# it6251_core.net
KiCad netlist of a schematic drawn in Altium Designer
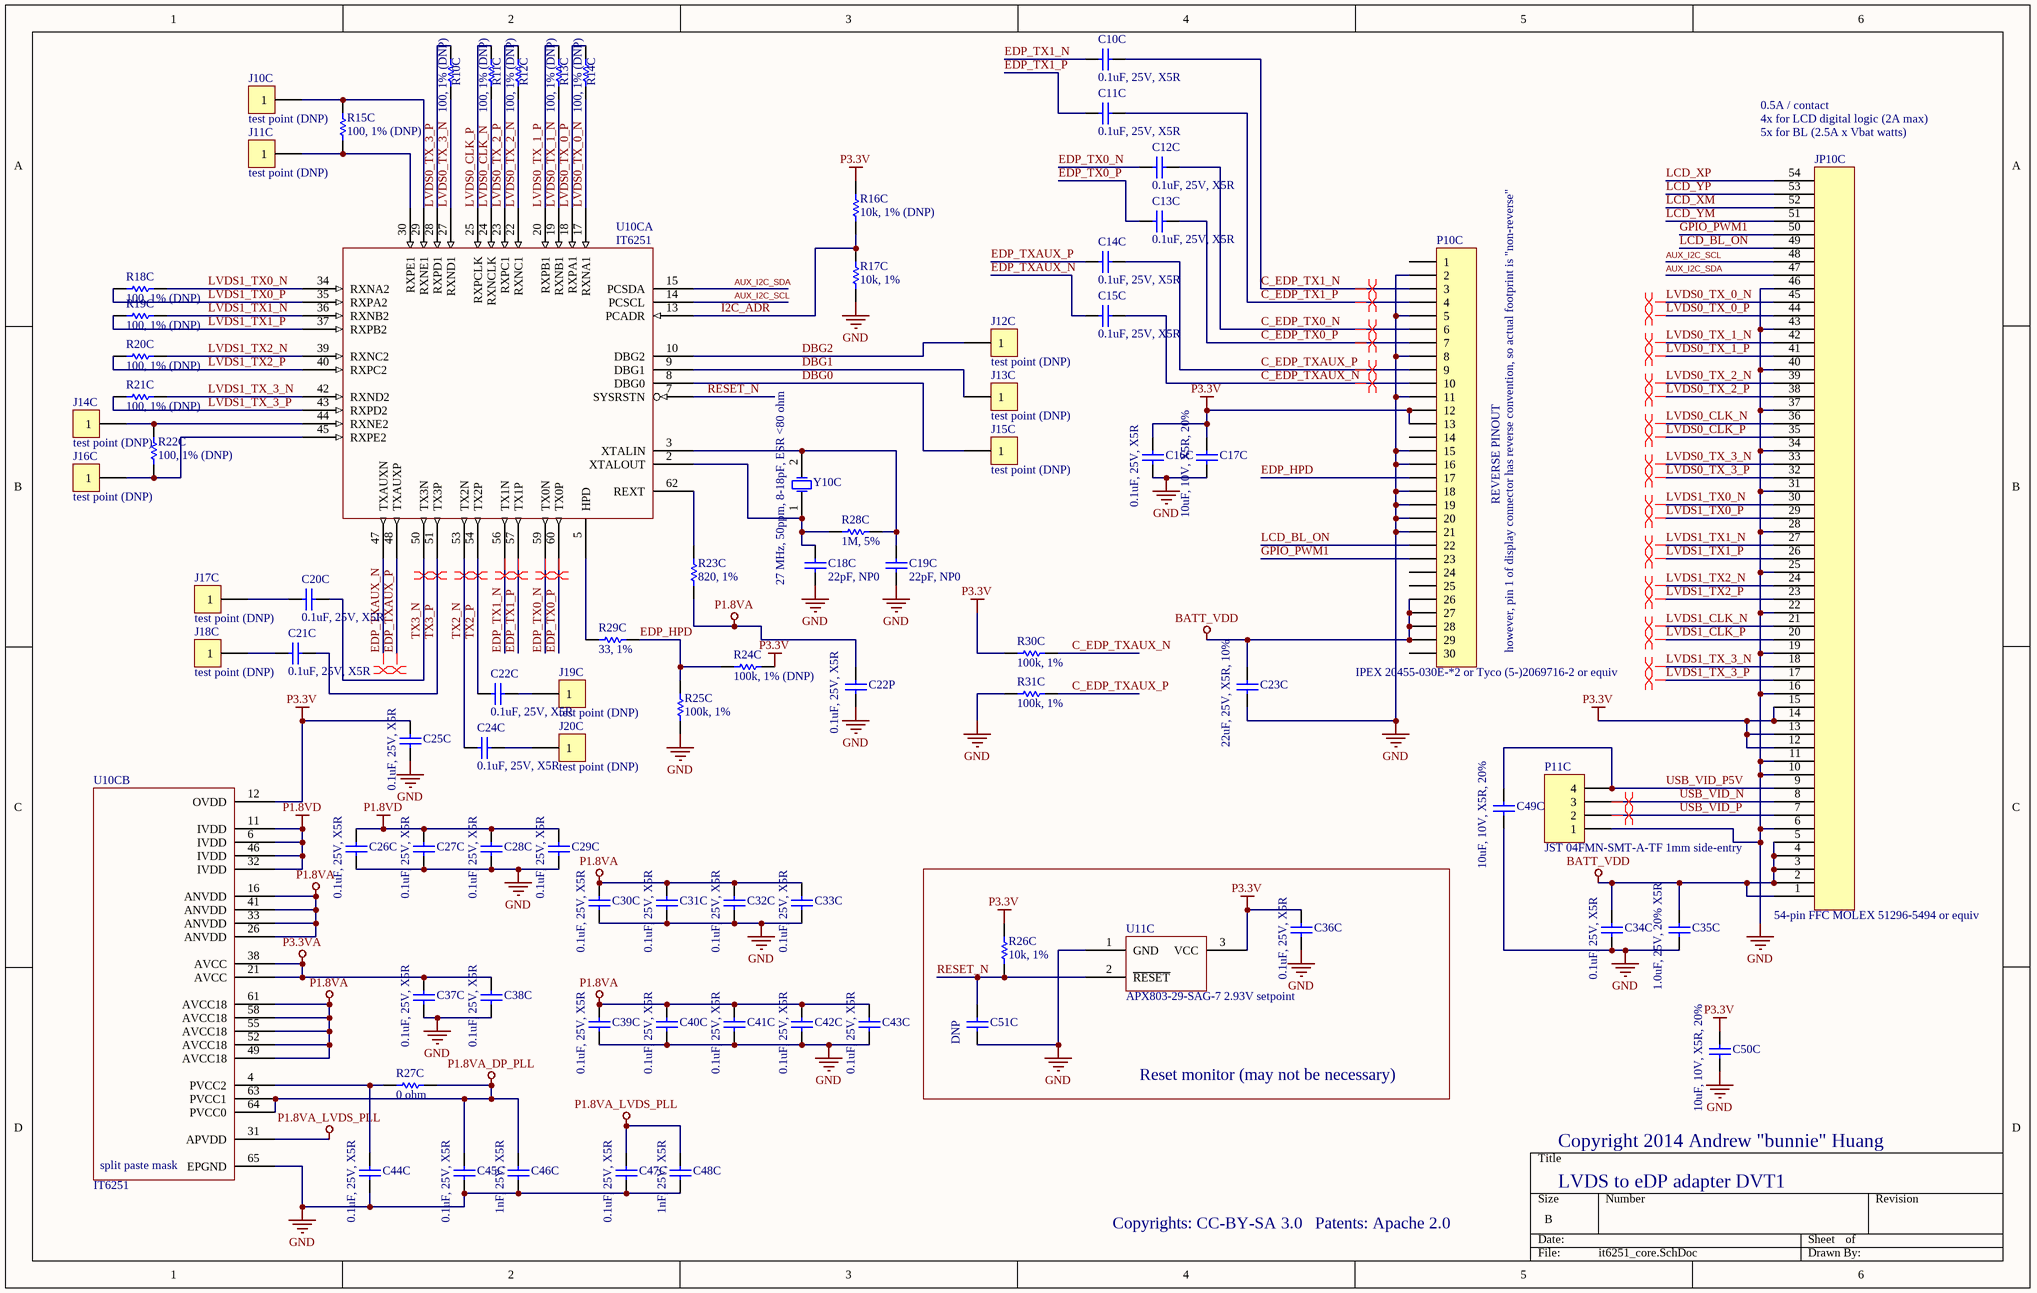
[diagram p0: it6251_core.SchDoc]

(export (version "E")
  (design (tool "Eeschema 10.0.6"))
  (components
    (comp (ref "C10C")
      (value "0.1uF, 25V, X5R")
      (footprint "CAPC1005N")
      (description "Capacitor (Semiconductor SIM Model)")
      (fields (field (name "PUBLISHER") "Altium Limited"))
      (libsource (lib "Miscellaneous Devices") (part "Cap Semi"))
    )
    (comp (ref "C11C")
      (value "0.1uF, 25V, X5R")
      (footprint "CAPC1005N")
      (description "Capacitor (Semiconductor SIM Model)")
      (fields (field (name "PUBLISHER") "Altium Limited"))
      (libsource (lib "Miscellaneous Devices") (part "Cap Semi"))
    )
    (comp (ref "C12C")
      (value "0.1uF, 25V, X5R")
      (footprint "CAPC1005N")
      (description "Capacitor (Semiconductor SIM Model)")
      (fields (field (name "PUBLISHER") "Altium Limited"))
      (libsource (lib "Miscellaneous Devices") (part "Cap Semi"))
    )
    (comp (ref "C13C")
      (value "0.1uF, 25V, X5R")
      (footprint "CAPC1005N")
      (description "Capacitor (Semiconductor SIM Model)")
      (fields (field (name "PUBLISHER") "Altium Limited"))
      (libsource (lib "Miscellaneous Devices") (part "Cap Semi"))
    )
    (comp (ref "C14C")
      (value "0.1uF, 25V, X5R")
      (footprint "CAPC1005N")
      (description "Capacitor (Semiconductor SIM Model)")
      (fields (field (name "PUBLISHER") "Altium Limited"))
      (libsource (lib "Miscellaneous Devices") (part "Cap Semi"))
    )
    (comp (ref "C15C")
      (value "0.1uF, 25V, X5R")
      (footprint "CAPC1005N")
      (description "Capacitor (Semiconductor SIM Model)")
      (fields (field (name "PUBLISHER") "Altium Limited"))
      (libsource (lib "Miscellaneous Devices") (part "Cap Semi"))
    )
    (comp (ref "C16C")
      (value "0.1uF, 25V, X5R")
      (footprint "CAPC1005N")
      (description "Capacitor (Semiconductor SIM Model)")
      (fields (field (name "PUBLISHER") "Altium Limited"))
      (libsource (lib "Miscellaneous Devices") (part "Cap Semi"))
    )
    (comp (ref "C17C")
      (value "10uF, 10V, X5R, 20%")
      (footprint "CAPC1608N")
      (description "Capacitor (Semiconductor SIM Model)")
      (fields (field (name "PUBLISHER") "Altium Limited"))
      (libsource (lib "Miscellaneous Devices") (part "Cap Semi"))
    )
    (comp (ref "C18C")
      (value "22pF, NP0")
      (footprint "CAPC1005N")
      (description "Capacitor (Semiconductor SIM Model)")
      (fields (field (name "PUBLISHER") "Altium Limited"))
      (libsource (lib "Miscellaneous Devices") (part "Cap Semi"))
    )
    (comp (ref "C19C")
      (value "22pF, NP0")
      (footprint "CAPC1005N")
      (description "Capacitor (Semiconductor SIM Model)")
      (fields (field (name "PUBLISHER") "Altium Limited"))
      (libsource (lib "Miscellaneous Devices") (part "Cap Semi"))
    )
    (comp (ref "C20C")
      (value "0.1uF, 25V, X5R")
      (footprint "CAPC1005N")
      (description "Capacitor (Semiconductor SIM Model)")
      (fields (field (name "PUBLISHER") "Altium Limited"))
      (libsource (lib "Miscellaneous Devices") (part "Cap Semi"))
    )
    (comp (ref "C21C")
      (value "0.1uF, 25V, X5R")
      (footprint "CAPC1005N")
      (description "Capacitor (Semiconductor SIM Model)")
      (fields (field (name "PUBLISHER") "Altium Limited"))
      (libsource (lib "Miscellaneous Devices") (part "Cap Semi"))
    )
    (comp (ref "C22C")
      (value "0.1uF, 25V, X5R")
      (footprint "CAPC1005N")
      (description "Capacitor (Semiconductor SIM Model)")
      (fields (field (name "PUBLISHER") "Altium Limited"))
      (libsource (lib "Miscellaneous Devices") (part "Cap Semi"))
    )
    (comp (ref "C22P")
      (value "0.1uF, 25V, X5R")
      (footprint "CAPC1005N")
      (description "Capacitor (Semiconductor SIM Model)")
      (fields (field (name "PUBLISHER") "Altium Limited"))
      (libsource (lib "Miscellaneous Devices") (part "Cap Semi"))
    )
    (comp (ref "C23C")
      (value "22uF, 25V, X5R, 10%")
      (footprint "CAPC3225N")
      (description "Capacitor (Semiconductor SIM Model)")
      (fields (field (name "PUBLISHER") "Altium Limited"))
      (libsource (lib "Miscellaneous Devices") (part "Cap Semi"))
    )
    (comp (ref "C24C")
      (value "0.1uF, 25V, X5R")
      (footprint "CAPC1005N")
      (description "Capacitor (Semiconductor SIM Model)")
      (fields (field (name "PUBLISHER") "Altium Limited"))
      (libsource (lib "Miscellaneous Devices") (part "Cap Semi"))
    )
    (comp (ref "C25C")
      (value "0.1uF, 25V, X5R")
      (footprint "CAPC1005N")
      (description "Capacitor (Semiconductor SIM Model)")
      (fields (field (name "PUBLISHER") "Altium Limited"))
      (libsource (lib "Miscellaneous Devices") (part "Cap Semi"))
    )
    (comp (ref "C26C")
      (value "0.1uF, 25V, X5R")
      (footprint "CAPC1005N")
      (description "Capacitor (Semiconductor SIM Model)")
      (fields (field (name "PUBLISHER") "Altium Limited"))
      (libsource (lib "Miscellaneous Devices") (part "Cap Semi"))
    )
    (comp (ref "C27C")
      (value "0.1uF, 25V, X5R")
      (footprint "CAPC1005N")
      (description "Capacitor (Semiconductor SIM Model)")
      (fields (field (name "PUBLISHER") "Altium Limited"))
      (libsource (lib "Miscellaneous Devices") (part "Cap Semi"))
    )
    (comp (ref "C28C")
      (value "0.1uF, 25V, X5R")
      (footprint "CAPC1005N")
      (description "Capacitor (Semiconductor SIM Model)")
      (fields (field (name "PUBLISHER") "Altium Limited"))
      (libsource (lib "Miscellaneous Devices") (part "Cap Semi"))
    )
    (comp (ref "C29C")
      (value "0.1uF, 25V, X5R")
      (footprint "CAPC1005N")
      (description "Capacitor (Semiconductor SIM Model)")
      (fields (field (name "PUBLISHER") "Altium Limited"))
      (libsource (lib "Miscellaneous Devices") (part "Cap Semi"))
    )
    (comp (ref "C30C")
      (value "0.1uF, 25V, X5R")
      (footprint "CAPC1005N")
      (description "Capacitor (Semiconductor SIM Model)")
      (fields (field (name "PUBLISHER") "Altium Limited"))
      (libsource (lib "Miscellaneous Devices") (part "Cap Semi"))
    )
    (comp (ref "C31C")
      (value "0.1uF, 25V, X5R")
      (footprint "CAPC1005N")
      (description "Capacitor (Semiconductor SIM Model)")
      (fields (field (name "PUBLISHER") "Altium Limited"))
      (libsource (lib "Miscellaneous Devices") (part "Cap Semi"))
    )
    (comp (ref "C32C")
      (value "0.1uF, 25V, X5R")
      (footprint "CAPC1005N")
      (description "Capacitor (Semiconductor SIM Model)")
      (fields (field (name "PUBLISHER") "Altium Limited"))
      (libsource (lib "Miscellaneous Devices") (part "Cap Semi"))
    )
    (comp (ref "C33C")
      (value "0.1uF, 25V, X5R")
      (footprint "CAPC1005N")
      (description "Capacitor (Semiconductor SIM Model)")
      (fields (field (name "PUBLISHER") "Altium Limited"))
      (libsource (lib "Miscellaneous Devices") (part "Cap Semi"))
    )
    (comp (ref "C34C")
      (value "0.1uF, 25V, X5R")
      (footprint "CAPC1005N")
      (description "Capacitor (Semiconductor SIM Model)")
      (fields (field (name "PUBLISHER") "Altium Limited"))
      (libsource (lib "Miscellaneous Devices") (part "Cap Semi"))
    )
    (comp (ref "C35C")
      (value "1.0uF, 25V, 20% X5R")
      (footprint "CAPC1608N")
      (description "Capacitor (Semiconductor SIM Model)")
      (fields (field (name "PUBLISHER") "Altium Limited"))
      (libsource (lib "Miscellaneous Devices") (part "Cap Semi"))
    )
    (comp (ref "C36C")
      (value "0.1uF, 25V, X5R")
      (footprint "CAPC1005N")
      (description "Capacitor (Semiconductor SIM Model)")
      (fields (field (name "PUBLISHER") "Altium Limited"))
      (libsource (lib "Miscellaneous Devices") (part "Cap Semi"))
    )
    (comp (ref "C37C")
      (value "0.1uF, 25V, X5R")
      (footprint "CAPC1005N")
      (description "Capacitor (Semiconductor SIM Model)")
      (fields (field (name "PUBLISHER") "Altium Limited"))
      (libsource (lib "Miscellaneous Devices") (part "Cap Semi"))
    )
    (comp (ref "C38C")
      (value "0.1uF, 25V, X5R")
      (footprint "CAPC1005N")
      (description "Capacitor (Semiconductor SIM Model)")
      (fields (field (name "PUBLISHER") "Altium Limited"))
      (libsource (lib "Miscellaneous Devices") (part "Cap Semi"))
    )
    (comp (ref "C39C")
      (value "0.1uF, 25V, X5R")
      (footprint "CAPC1005N")
      (description "Capacitor (Semiconductor SIM Model)")
      (fields (field (name "PUBLISHER") "Altium Limited"))
      (libsource (lib "Miscellaneous Devices") (part "Cap Semi"))
    )
    (comp (ref "C40C")
      (value "0.1uF, 25V, X5R")
      (footprint "CAPC1005N")
      (description "Capacitor (Semiconductor SIM Model)")
      (fields (field (name "PUBLISHER") "Altium Limited"))
      (libsource (lib "Miscellaneous Devices") (part "Cap Semi"))
    )
    (comp (ref "C41C")
      (value "0.1uF, 25V, X5R")
      (footprint "CAPC1005N")
      (description "Capacitor (Semiconductor SIM Model)")
      (fields (field (name "PUBLISHER") "Altium Limited"))
      (libsource (lib "Miscellaneous Devices") (part "Cap Semi"))
    )
    (comp (ref "C42C")
      (value "0.1uF, 25V, X5R")
      (footprint "CAPC1005N")
      (description "Capacitor (Semiconductor SIM Model)")
      (fields (field (name "PUBLISHER") "Altium Limited"))
      (libsource (lib "Miscellaneous Devices") (part "Cap Semi"))
    )
    (comp (ref "C43C")
      (value "0.1uF, 25V, X5R")
      (footprint "CAPC1005N")
      (description "Capacitor (Semiconductor SIM Model)")
      (fields (field (name "PUBLISHER") "Altium Limited"))
      (libsource (lib "Miscellaneous Devices") (part "Cap Semi"))
    )
    (comp (ref "C44C")
      (value "0.1uF, 25V, X5R")
      (footprint "CAPC1005N")
      (description "Capacitor (Semiconductor SIM Model)")
      (fields (field (name "PUBLISHER") "Altium Limited"))
      (libsource (lib "Miscellaneous Devices") (part "Cap Semi"))
    )
    (comp (ref "C45C")
      (value "0.1uF, 25V, X5R")
      (footprint "CAPC1005N")
      (description "Capacitor (Semiconductor SIM Model)")
      (fields (field (name "PUBLISHER") "Altium Limited"))
      (libsource (lib "Miscellaneous Devices") (part "Cap Semi"))
    )
    (comp (ref "C46C")
      (value "1nF, 25V, X5R")
      (footprint "CAPC1005N")
      (description "Capacitor (Semiconductor SIM Model)")
      (fields (field (name "PUBLISHER") "Altium Limited"))
      (libsource (lib "Miscellaneous Devices") (part "Cap Semi"))
    )
    (comp (ref "C47C")
      (value "0.1uF, 25V, X5R")
      (footprint "CAPC1005N")
      (description "Capacitor (Semiconductor SIM Model)")
      (fields (field (name "PUBLISHER") "Altium Limited"))
      (libsource (lib "Miscellaneous Devices") (part "Cap Semi"))
    )
    (comp (ref "C48C")
      (value "1nF, 25V, X5R")
      (footprint "CAPC1005N")
      (description "Capacitor (Semiconductor SIM Model)")
      (fields (field (name "PUBLISHER") "Altium Limited"))
      (libsource (lib "Miscellaneous Devices") (part "Cap Semi"))
    )
    (comp (ref "C49C")
      (value "10uF, 10V, X5R, 20%")
      (footprint "CAPC1608N")
      (description "Capacitor (Semiconductor SIM Model)")
      (fields (field (name "PUBLISHER") "Altium Limited"))
      (libsource (lib "Miscellaneous Devices") (part "Cap Semi"))
    )
    (comp (ref "C50C")
      (value "10uF, 10V, X5R, 20%")
      (footprint "CAPC1608N")
      (description "Capacitor (Semiconductor SIM Model)")
      (fields (field (name "PUBLISHER") "Altium Limited"))
      (libsource (lib "Miscellaneous Devices") (part "Cap Semi"))
    )
    (comp (ref "C51C")
      (value "DNP")
      (footprint "CAPC1608N")
      (description "Capacitor (Semiconductor SIM Model)")
      (fields (field (name "PUBLISHER") "Altium Limited"))
      (libsource (lib "Miscellaneous Devices") (part "Cap Semi"))
    )
    (comp (ref "J10C")
      (value "test point (DNP)")
      (footprint "TP_SMT_38mil")
      (description "Connector")
      (libsource (lib "") (part "CON1_1"))
    )
    (comp (ref "J11C")
      (value "test point (DNP)")
      (footprint "TP_SMT_38mil")
      (description "Connector")
      (libsource (lib "") (part "CON1_1"))
    )
    (comp (ref "J12C")
      (value "test point (DNP)")
      (footprint "TP_SMT_38mil")
      (description "Connector")
      (libsource (lib "*") (part "CON1"))
    )
    (comp (ref "J13C")
      (value "test point (DNP)")
      (footprint "TP_SMT_38mil")
      (description "Connector")
      (libsource (lib "*") (part "CON1"))
    )
    (comp (ref "J14C")
      (value "test point (DNP)")
      (footprint "TP_SMT_38mil")
      (description "Connector")
      (libsource (lib "") (part "CON1_1"))
    )
    (comp (ref "J15C")
      (value "test point (DNP)")
      (footprint "TP_SMT_38mil")
      (description "Connector")
      (libsource (lib "*") (part "CON1"))
    )
    (comp (ref "J16C")
      (value "test point (DNP)")
      (footprint "TP_SMT_38mil")
      (description "Connector")
      (libsource (lib "") (part "CON1_1"))
    )
    (comp (ref "J17C")
      (value "test point (DNP)")
      (footprint "TP_SMT_38mil")
      (description "Connector")
      (libsource (lib "") (part "CON1_1"))
    )
    (comp (ref "J18C")
      (value "test point (DNP)")
      (footprint "TP_SMT_38mil")
      (description "Connector")
      (libsource (lib "") (part "CON1_1"))
    )
    (comp (ref "J19C")
      (value "test point (DNP)")
      (footprint "TP_SMT_38mil")
      (description "Connector")
      (libsource (lib "*") (part "CON1"))
    )
    (comp (ref "J20C")
      (value "test point (DNP)")
      (footprint "TP_SMT_38mil")
      (description "Connector")
      (libsource (lib "*") (part "CON1"))
    )
    (comp (ref "JP10C")
      (value "54-pin FFC MOLEX 51296-5494 or equiv")
      (footprint "MOLEX_51296_5494")
      (description "Flat flex connector, 54 positions")
      (libsource (lib "commonsch") (part "HEADER_54"))
    )
    (comp (ref "P10C")
      (value "IPEX 20455-030E-*2 or Tyco (5-)2069716-2 or equiv")
      (footprint "TYCO_5-2069716-2")
      (fields (field (name "PUBLISHER") "Altium Limited"))
      (libsource (lib "Miscellaneous Connectors") (part "Header 30"))
    )
    (comp (ref "P11C")
      (value "JST 04FMN-SMT-A-TF 1mm side-entry")
      (footprint "JST_04FMN_SMT_A_TF")
      (description "Header, 4-Pin")
      (fields (field (name "PUBLISHER") "Altium Limited"))
      (libsource (lib "Miscellaneous Connectors") (part "Header 4"))
    )
    (comp (ref "R10C")
      (value "100, 1% (DNP)")
      (footprint "RESC0603N")
      (description "Resistor")
      (fields (field (name "PUBLISHER") "Altium Limited"))
      (libsource (lib "Miscellaneous Devices") (part "Res1"))
    )
    (comp (ref "R11C")
      (value "100, 1% (DNP)")
      (footprint "RESC0603N")
      (description "Resistor")
      (fields (field (name "PUBLISHER") "Altium Limited"))
      (libsource (lib "Miscellaneous Devices") (part "Res1"))
    )
    (comp (ref "R12C")
      (value "100, 1% (DNP)")
      (footprint "RESC0603N")
      (description "Resistor")
      (fields (field (name "PUBLISHER") "Altium Limited"))
      (libsource (lib "Miscellaneous Devices") (part "Res1"))
    )
    (comp (ref "R13C")
      (value "100, 1% (DNP)")
      (footprint "RESC0603N")
      (description "Resistor")
      (fields (field (name "PUBLISHER") "Altium Limited"))
      (libsource (lib "Miscellaneous Devices") (part "Res1"))
    )
    (comp (ref "R14C")
      (value "100, 1% (DNP)")
      (footprint "RESC0603N")
      (description "Resistor")
      (fields (field (name "PUBLISHER") "Altium Limited"))
      (libsource (lib "Miscellaneous Devices") (part "Res1"))
    )
    (comp (ref "R15C")
      (value "100, 1% (DNP)")
      (footprint "RESC0603N")
      (description "Resistor")
      (fields (field (name "PUBLISHER") "Altium Limited"))
      (libsource (lib "Miscellaneous Devices") (part "Res1"))
    )
    (comp (ref "R16C")
      (value "10k, 1% (DNP)")
      (footprint "RESC1005N")
      (description "Resistor")
      (fields (field (name "PUBLISHER") "Altium Limited"))
      (libsource (lib "Miscellaneous Devices") (part "Res1"))
    )
    (comp (ref "R17C")
      (value "10k, 1%")
      (footprint "RESC1005N")
      (description "Resistor")
      (fields (field (name "PUBLISHER") "Altium Limited"))
      (libsource (lib "Miscellaneous Devices") (part "Res1"))
    )
    (comp (ref "R18C")
      (value "100, 1% (DNP)")
      (footprint "RESC0603N")
      (description "Resistor")
      (fields (field (name "PUBLISHER") "Altium Limited"))
      (libsource (lib "Miscellaneous Devices") (part "Res1"))
    )
    (comp (ref "R19C")
      (value "100, 1% (DNP)")
      (footprint "RESC0603N")
      (description "Resistor")
      (fields (field (name "PUBLISHER") "Altium Limited"))
      (libsource (lib "Miscellaneous Devices") (part "Res1"))
    )
    (comp (ref "R20C")
      (value "100, 1% (DNP)")
      (footprint "RESC0603N")
      (description "Resistor")
      (fields (field (name "PUBLISHER") "Altium Limited"))
      (libsource (lib "Miscellaneous Devices") (part "Res1"))
    )
    (comp (ref "R21C")
      (value "100, 1% (DNP)")
      (footprint "RESC0603N")
      (description "Resistor")
      (fields (field (name "PUBLISHER") "Altium Limited"))
      (libsource (lib "Miscellaneous Devices") (part "Res1"))
    )
    (comp (ref "R22C")
      (value "100, 1% (DNP)")
      (footprint "RESC0603N")
      (description "Resistor")
      (fields (field (name "PUBLISHER") "Altium Limited"))
      (libsource (lib "Miscellaneous Devices") (part "Res1"))
    )
    (comp (ref "R23C")
      (value "820, 1%")
      (footprint "RESC1005N")
      (description "Resistor")
      (fields (field (name "PUBLISHER") "Altium Limited"))
      (libsource (lib "Miscellaneous Devices") (part "Res1"))
    )
    (comp (ref "R24C")
      (value "100k, 1% (DNP)")
      (footprint "RESC1005N")
      (description "Resistor")
      (fields (field (name "PUBLISHER") "Altium Limited"))
      (libsource (lib "Miscellaneous Devices") (part "Res1"))
    )
    (comp (ref "R25C")
      (value "100k, 1%")
      (footprint "RESC1005N")
      (description "Resistor")
      (fields (field (name "PUBLISHER") "Altium Limited"))
      (libsource (lib "Miscellaneous Devices") (part "Res1"))
    )
    (comp (ref "R26C")
      (value "10k, 1%")
      (footprint "RESC1005N")
      (description "Resistor")
      (fields (field (name "PUBLISHER") "Altium Limited"))
      (libsource (lib "Miscellaneous Devices") (part "Res1"))
    )
    (comp (ref "R27C")
      (value "0 ohm")
      (footprint "RESC1005N")
      (description "Resistor")
      (fields (field (name "PUBLISHER") "Altium Limited"))
      (libsource (lib "Miscellaneous Devices") (part "Res1"))
    )
    (comp (ref "R28C")
      (value "1M, 5%")
      (footprint "RESC1005N")
      (description "Resistor")
      (fields (field (name "PUBLISHER") "Altium Limited"))
      (libsource (lib "Miscellaneous Devices") (part "Res1"))
    )
    (comp (ref "R29C")
      (value "33, 1%")
      (footprint "RESC1005N")
      (description "Resistor")
      (fields (field (name "PUBLISHER") "Altium Limited"))
      (libsource (lib "Miscellaneous Devices") (part "Res1"))
    )
    (comp (ref "R30C")
      (value "100k, 1%")
      (footprint "RESC1005N")
      (description "Resistor")
      (fields (field (name "PUBLISHER") "Altium Limited"))
      (libsource (lib "Miscellaneous Devices") (part "Res1"))
    )
    (comp (ref "R31C")
      (value "100k, 1%")
      (footprint "RESC1005N")
      (description "Resistor")
      (fields (field (name "PUBLISHER") "Altium Limited"))
      (libsource (lib "Miscellaneous Devices") (part "Res1"))
    )
    (comp (ref "U10C")
      (value "IT6251")
      (footprint "QFN50P900X900-64WAN")
      (description "LVDS to eDP converter")
      (libsource (lib "commonsch") (part "IT6251"))
    )
    (comp (ref "U11C")
      (value "APX803-29-SAG-7 2.93V setpoint")
      (footprint "SOT23-3N")
      (description "Reset monitor. Voltage specified by XX in P/N. Multiple vendors.")
      (libsource (lib "commonsch") (part "RESET_SOT23"))
    )
    (comp (ref "Y10C")
      (value "27 MHz, 50ppm, 8-18pF, ESR <80 ohm")
      (footprint "NDK_NX5032A")
      (description "Crystal Oscillator")
      (fields (field (name "PUBLISHER") "Altium Limited"))
      (libsource (lib "Miscellaneous Devices") (part "XTAL"))
    )
  )
  (nets
    (net (code "1") (name "/AUX_I2C_SCL") (class "Default")
      (node (ref "JP10C") (pin "48") (pintype "passive"))
      (node (ref "U10C") (pin "14") (pinfunction "PCSCL_14") (pintype "open_collector"))
    )
    (net (code "2") (name "/AUX_I2C_SDA") (class "Default")
      (node (ref "JP10C") (pin "47") (pintype "passive"))
      (node (ref "U10C") (pin "15") (pinfunction "PCSDA_15") (pintype "open_collector"))
    )
    (net (code "3") (name "/C_EDP_TX0_N") (class "Default")
      (node (ref "C12C") (pin "1") (pinfunction "1_1") (pintype "passive"))
      (node (ref "P10C") (pin "6") (pinfunction "6_6") (pintype "passive"))
    )
    (net (code "4") (name "/C_EDP_TX0_P") (class "Default")
      (node (ref "C13C") (pin "1") (pinfunction "1_1") (pintype "passive"))
      (node (ref "P10C") (pin "7") (pinfunction "7_7") (pintype "passive"))
    )
    (net (code "5") (name "/C_EDP_TX1_N") (class "Default")
      (node (ref "C10C") (pin "1") (pinfunction "1_1") (pintype "passive"))
      (node (ref "P10C") (pin "3") (pinfunction "3_3") (pintype "passive"))
    )
    (net (code "6") (name "/C_EDP_TX1_P") (class "Default")
      (node (ref "C11C") (pin "1") (pinfunction "1_1") (pintype "passive"))
      (node (ref "P10C") (pin "4") (pinfunction "4_4") (pintype "passive"))
    )
    (net (code "7") (name "/C_EDP_TXAUX_N") (class "Default")
      (node (ref "C15C") (pin "1") (pinfunction "1_1") (pintype "passive"))
      (node (ref "P10C") (pin "10") (pinfunction "10_10") (pintype "passive"))
      (node (ref "R30C") (pin "1") (pinfunction "1_1") (pintype "passive"))
    )
    (net (code "8") (name "/C_EDP_TXAUX_P") (class "Default")
      (node (ref "C14C") (pin "1") (pinfunction "1_1") (pintype "passive"))
      (node (ref "P10C") (pin "9") (pinfunction "9_9") (pintype "passive"))
      (node (ref "R31C") (pin "1") (pinfunction "1_1") (pintype "passive"))
    )
    (net (code "9") (name "/DBG0") (class "Default")
      (node (ref "J15C") (pin "1") (pinfunction "1_1") (pintype "passive"))
      (node (ref "U10C") (pin "8") (pinfunction "DBG0_8") (pintype "passive"))
    )
    (net (code "10") (name "/DBG1") (class "Default")
      (node (ref "J13C") (pin "1") (pinfunction "1_1") (pintype "passive"))
      (node (ref "U10C") (pin "9") (pinfunction "DBG1_9") (pintype "passive"))
    )
    (net (code "11") (name "/DBG2") (class "Default")
      (node (ref "J12C") (pin "1") (pinfunction "1_1") (pintype "passive"))
      (node (ref "U10C") (pin "10") (pinfunction "DBG2_10") (pintype "passive"))
    )
    (net (code "12") (name "/EDP_HPD") (class "Default")
      (node (ref "P10C") (pin "17") (pinfunction "17_17") (pintype "passive"))
      (node (ref "R24C") (pin "2") (pinfunction "2_2") (pintype "passive"))
      (node (ref "R25C") (pin "1") (pinfunction "1_1") (pintype "passive"))
      (node (ref "R29C") (pin "2") (pinfunction "2_2") (pintype "passive"))
    )
    (net (code "13") (name "/EDP_TX0_N") (class "Default")
      (node (ref "C12C") (pin "2") (pinfunction "2_2") (pintype "passive"))
      (node (ref "U10C") (pin "59") (pinfunction "TX0N_59") (pintype "output"))
    )
    (net (code "14") (name "/EDP_TX0_P") (class "Default")
      (node (ref "C13C") (pin "2") (pinfunction "2_2") (pintype "passive"))
      (node (ref "U10C") (pin "60") (pinfunction "TX0P_60") (pintype "output"))
    )
    (net (code "15") (name "/EDP_TX1_N") (class "Default")
      (node (ref "C10C") (pin "2") (pinfunction "2_2") (pintype "passive"))
      (node (ref "U10C") (pin "56") (pinfunction "TX1N_56") (pintype "output"))
    )
    (net (code "16") (name "/EDP_TX1_P") (class "Default")
      (node (ref "C11C") (pin "2") (pinfunction "2_2") (pintype "passive"))
      (node (ref "U10C") (pin "57") (pinfunction "TX1P_57") (pintype "output"))
    )
    (net (code "17") (name "/EDP_TXAUX_N") (class "Default")
      (node (ref "C15C") (pin "2") (pinfunction "2_2") (pintype "passive"))
      (node (ref "U10C") (pin "47") (pinfunction "TXAUXN_47") (pintype "output"))
    )
    (net (code "18") (name "/EDP_TXAUX_P") (class "Default")
      (node (ref "C14C") (pin "2") (pinfunction "2_2") (pintype "passive"))
      (node (ref "U10C") (pin "48") (pinfunction "TXAUXP_48") (pintype "output"))
    )
    (net (code "19") (name "/GPIO_PWM1") (class "Default")
      (node (ref "JP10C") (pin "50") (pintype "passive"))
      (node (ref "P10C") (pin "23") (pinfunction "23_23") (pintype "passive"))
    )
    (net (code "20") (name "/I2C_ADR") (class "Default")
      (node (ref "R16C") (pin "2") (pinfunction "2_2") (pintype "passive"))
      (node (ref "R17C") (pin "1") (pinfunction "1_1") (pintype "passive"))
      (node (ref "U10C") (pin "13") (pinfunction "PCADR_13") (pintype "input"))
    )
    (net (code "21") (name "/LCD_BL_ON") (class "Default")
      (node (ref "JP10C") (pin "49") (pintype "passive"))
      (node (ref "P10C") (pin "22") (pinfunction "22_22") (pintype "passive"))
    )
    (net (code "22") (name "/LCD_XM") (class "Default") (node (ref "JP10C") (pin "52") (pintype "passive")))
    (net (code "23") (name "/LCD_XP") (class "Default") (node (ref "JP10C") (pin "54") (pintype "passive")))
    (net (code "24") (name "/LCD_YM") (class "Default") (node (ref "JP10C") (pin "51") (pintype "passive")))
    (net (code "25") (name "/LCD_YP") (class "Default") (node (ref "JP10C") (pin "53") (pintype "passive")))
    (net (code "26") (name "/LVDS0_CLK_N") (class "Default")
      (node (ref "JP10C") (pin "36") (pintype "passive"))
      (node (ref "R11C") (pin "2") (pinfunction "2_2") (pintype "passive"))
      (node (ref "U10C") (pin "24") (pinfunction "RXNCLK_24") (pintype "input"))
    )
    (net (code "27") (name "/LVDS0_CLK_P") (class "Default")
      (node (ref "JP10C") (pin "35") (pintype "passive"))
      (node (ref "R11C") (pin "1") (pinfunction "1_1") (pintype "passive"))
      (node (ref "U10C") (pin "25") (pinfunction "RXPCLK_25") (pintype "input"))
    )
    (net (code "28") (name "/LVDS0_TX_0_N") (class "Default")
      (node (ref "JP10C") (pin "45") (pintype "passive"))
      (node (ref "R14C") (pin "2") (pinfunction "2_2") (pintype "passive"))
      (node (ref "U10C") (pin "17") (pinfunction "RXNA1_17") (pintype "input"))
    )
    (net (code "29") (name "/LVDS0_TX_0_P") (class "Default")
      (node (ref "JP10C") (pin "44") (pintype "passive"))
      (node (ref "R14C") (pin "1") (pinfunction "1_1") (pintype "passive"))
      (node (ref "U10C") (pin "18") (pinfunction "RXPA1_18") (pintype "input"))
    )
    (net (code "30") (name "/LVDS0_TX_1_N") (class "Default")
      (node (ref "JP10C") (pin "42") (pintype "passive"))
      (node (ref "R13C") (pin "2") (pinfunction "2_2") (pintype "passive"))
      (node (ref "U10C") (pin "19") (pinfunction "RXNB1_19") (pintype "input"))
    )
    (net (code "31") (name "/LVDS0_TX_1_P") (class "Default")
      (node (ref "JP10C") (pin "41") (pintype "passive"))
      (node (ref "R13C") (pin "1") (pinfunction "1_1") (pintype "passive"))
      (node (ref "U10C") (pin "20") (pinfunction "RXPB1_20") (pintype "input"))
    )
    (net (code "32") (name "/LVDS0_TX_2_N") (class "Default")
      (node (ref "JP10C") (pin "39") (pintype "passive"))
      (node (ref "R12C") (pin "2") (pinfunction "2_2") (pintype "passive"))
      (node (ref "U10C") (pin "22") (pinfunction "RXNC1_22") (pintype "input"))
    )
    (net (code "33") (name "/LVDS0_TX_2_P") (class "Default")
      (node (ref "JP10C") (pin "38") (pintype "passive"))
      (node (ref "R12C") (pin "1") (pinfunction "1_1") (pintype "passive"))
      (node (ref "U10C") (pin "23") (pinfunction "RXPC1_23") (pintype "input"))
    )
    (net (code "34") (name "/LVDS0_TX_3_N") (class "Default")
      (node (ref "JP10C") (pin "33") (pintype "passive"))
      (node (ref "R10C") (pin "2") (pinfunction "2_2") (pintype "passive"))
      (node (ref "U10C") (pin "27") (pinfunction "RXND1_27") (pintype "input"))
    )
    (net (code "35") (name "/LVDS0_TX_3_P") (class "Default")
      (node (ref "JP10C") (pin "32") (pintype "passive"))
      (node (ref "R10C") (pin "1") (pinfunction "1_1") (pintype "passive"))
      (node (ref "U10C") (pin "28") (pinfunction "RXPD1_28") (pintype "input"))
    )
    (net (code "36") (name "/LVDS1_CLK_N") (class "Default")
      (node (ref "JP10C") (pin "21") (pintype "passive"))
    )
    (net (code "37") (name "/LVDS1_CLK_P") (class "Default")
      (node (ref "JP10C") (pin "20") (pintype "passive"))
    )
    (net (code "38") (name "/LVDS1_TX0_N") (class "Default")
      (node (ref "JP10C") (pin "30") (pintype "passive"))
      (node (ref "R18C") (pin "1") (pinfunction "1_1") (pintype "passive"))
      (node (ref "U10C") (pin "34") (pinfunction "RXNA2_34") (pintype "input"))
    )
    (net (code "39") (name "/LVDS1_TX0_P") (class "Default")
      (node (ref "JP10C") (pin "29") (pintype "passive"))
      (node (ref "R18C") (pin "2") (pinfunction "2_2") (pintype "passive"))
      (node (ref "U10C") (pin "35") (pinfunction "RXPA2_35") (pintype "input"))
    )
    (net (code "40") (name "/LVDS1_TX1_N") (class "Default")
      (node (ref "JP10C") (pin "27") (pintype "passive"))
      (node (ref "R19C") (pin "1") (pinfunction "1_1") (pintype "passive"))
      (node (ref "U10C") (pin "36") (pinfunction "RXNB2_36") (pintype "input"))
    )
    (net (code "41") (name "/LVDS1_TX1_P") (class "Default")
      (node (ref "JP10C") (pin "26") (pintype "passive"))
      (node (ref "R19C") (pin "2") (pinfunction "2_2") (pintype "passive"))
      (node (ref "U10C") (pin "37") (pinfunction "RXPB2_37") (pintype "input"))
    )
    (net (code "42") (name "/LVDS1_TX2_N") (class "Default")
      (node (ref "JP10C") (pin "24") (pintype "passive"))
      (node (ref "R20C") (pin "1") (pinfunction "1_1") (pintype "passive"))
      (node (ref "U10C") (pin "39") (pinfunction "RXNC2_39") (pintype "input"))
    )
    (net (code "43") (name "/LVDS1_TX2_P") (class "Default")
      (node (ref "JP10C") (pin "23") (pintype "passive"))
      (node (ref "R20C") (pin "2") (pinfunction "2_2") (pintype "passive"))
      (node (ref "U10C") (pin "40") (pinfunction "RXPC2_40") (pintype "input"))
    )
    (net (code "44") (name "/LVDS1_TX_3_N") (class "Default")
      (node (ref "JP10C") (pin "18") (pintype "passive"))
      (node (ref "R21C") (pin "1") (pinfunction "1_1") (pintype "passive"))
      (node (ref "U10C") (pin "42") (pinfunction "RXND2_42") (pintype "input"))
    )
    (net (code "45") (name "/LVDS1_TX_3_P") (class "Default")
      (node (ref "JP10C") (pin "17") (pintype "passive"))
      (node (ref "R21C") (pin "2") (pinfunction "2_2") (pintype "passive"))
      (node (ref "U10C") (pin "43") (pinfunction "RXPD2_43") (pintype "input"))
    )
    (net (code "46") (name "/RESET_N") (class "Default")
      (node (ref "C51C") (pin "1") (pinfunction "1_1") (pintype "passive"))
      (node (ref "R26C") (pin "2") (pinfunction "2_2") (pintype "passive"))
      (node (ref "U10C") (pin "7") (pinfunction "SYSRSTN_7") (pintype "input"))
      (node (ref "U11C") (pin "2") (pinfunction "~{RESET}_2") (pintype "open_collector"))
    )
    (net (code "47") (name "/TX2_N") (class "Default")
      (node (ref "C24C") (pin "2") (pinfunction "2_2") (pintype "passive"))
      (node (ref "U10C") (pin "53") (pinfunction "TX2N_53") (pintype "output"))
    )
    (net (code "48") (name "/TX2_P") (class "Default")
      (node (ref "C22C") (pin "2") (pinfunction "2_2") (pintype "passive"))
      (node (ref "U10C") (pin "54") (pinfunction "TX2P_54") (pintype "output"))
    )
    (net (code "49") (name "/TX3_N") (class "Default")
      (node (ref "C20C") (pin "1") (pinfunction "1_1") (pintype "passive"))
      (node (ref "U10C") (pin "50") (pinfunction "TX3N_50") (pintype "output"))
    )
    (net (code "50") (name "/TX3_P") (class "Default")
      (node (ref "C21C") (pin "1") (pinfunction "1_1") (pintype "passive"))
      (node (ref "U10C") (pin "51") (pinfunction "TX3P_51") (pintype "output"))
    )
    (net (code "51") (name "/USB_VID_N") (class "Default")
      (node (ref "JP10C") (pin "8") (pintype "passive"))
      (node (ref "P11C") (pin "3") (pinfunction "3_3") (pintype "passive"))
    )
    (net (code "52") (name "/USB_VID_P") (class "Default")
      (node (ref "JP10C") (pin "7") (pintype "passive"))
      (node (ref "P11C") (pin "2") (pinfunction "2_2") (pintype "passive"))
    )
    (net (code "53") (name "/USB_VID_P5V") (class "Default")
      (node (ref "C49C") (pin "2") (pinfunction "2_2") (pintype "passive"))
      (node (ref "JP10C") (pin "9") (pintype "passive"))
      (node (ref "P11C") (pin "4") (pinfunction "4_4") (pintype "passive"))
    )
    (net (code "54") (name "BATT_VDD") (class "Default")
      (node (ref "C23C") (pin "1") (pinfunction "1_1") (pintype "passive"))
      (node (ref "C34C") (pin "1") (pinfunction "1_1") (pintype "passive"))
      (node (ref "C35C") (pin "1") (pinfunction "1_1") (pintype "passive"))
      (node (ref "JP10C") (pin "1") (pintype "passive"))
      (node (ref "JP10C") (pin "2") (pintype "passive"))
      (node (ref "JP10C") (pin "3") (pintype "passive"))
      (node (ref "JP10C") (pin "4") (pintype "passive"))
      (node (ref "JP10C") (pin "5") (pintype "passive"))
      (node (ref "P10C") (pin "26") (pinfunction "26_26") (pintype "passive"))
      (node (ref "P10C") (pin "27") (pinfunction "27_27") (pintype "passive"))
      (node (ref "P10C") (pin "28") (pinfunction "28_28") (pintype "passive"))
      (node (ref "P10C") (pin "29") (pinfunction "29_29") (pintype "passive"))
    )
    (net (code "55") (name "GND") (class "Default")
      (node (ref "C16C") (pin "2") (pinfunction "2_2") (pintype "passive"))
      (node (ref "C17C") (pin "1") (pinfunction "1_1") (pintype "passive"))
      (node (ref "C18C") (pin "1") (pinfunction "1_1") (pintype "passive"))
      (node (ref "C19C") (pin "1") (pinfunction "1_1") (pintype "passive"))
      (node (ref "C22P") (pin "1") (pinfunction "1_1") (pintype "passive"))
      (node (ref "C23C") (pin "2") (pinfunction "2_2") (pintype "passive"))
      (node (ref "C25C") (pin "2") (pinfunction "2_2") (pintype "passive"))
      (node (ref "C26C") (pin "2") (pinfunction "2_2") (pintype "passive"))
      (node (ref "C27C") (pin "2") (pinfunction "2_2") (pintype "passive"))
      (node (ref "C28C") (pin "2") (pinfunction "2_2") (pintype "passive"))
      (node (ref "C29C") (pin "2") (pinfunction "2_2") (pintype "passive"))
      (node (ref "C30C") (pin "2") (pinfunction "2_2") (pintype "passive"))
      (node (ref "C31C") (pin "2") (pinfunction "2_2") (pintype "passive"))
      (node (ref "C32C") (pin "2") (pinfunction "2_2") (pintype "passive"))
      (node (ref "C33C") (pin "2") (pinfunction "2_2") (pintype "passive"))
      (node (ref "C34C") (pin "2") (pinfunction "2_2") (pintype "passive"))
      (node (ref "C35C") (pin "2") (pinfunction "2_2") (pintype "passive"))
      (node (ref "C36C") (pin "2") (pinfunction "2_2") (pintype "passive"))
      (node (ref "C37C") (pin "2") (pinfunction "2_2") (pintype "passive"))
      (node (ref "C38C") (pin "2") (pinfunction "2_2") (pintype "passive"))
      (node (ref "C39C") (pin "2") (pinfunction "2_2") (pintype "passive"))
      (node (ref "C40C") (pin "2") (pinfunction "2_2") (pintype "passive"))
      (node (ref "C41C") (pin "2") (pinfunction "2_2") (pintype "passive"))
      (node (ref "C42C") (pin "2") (pinfunction "2_2") (pintype "passive"))
      (node (ref "C43C") (pin "2") (pinfunction "2_2") (pintype "passive"))
      (node (ref "C44C") (pin "2") (pinfunction "2_2") (pintype "passive"))
      (node (ref "C45C") (pin "2") (pinfunction "2_2") (pintype "passive"))
      (node (ref "C46C") (pin "2") (pinfunction "2_2") (pintype "passive"))
      (node (ref "C47C") (pin "2") (pinfunction "2_2") (pintype "passive"))
      (node (ref "C48C") (pin "2") (pinfunction "2_2") (pintype "passive"))
      (node (ref "C49C") (pin "1") (pinfunction "1_1") (pintype "passive"))
      (node (ref "C50C") (pin "1") (pinfunction "1_1") (pintype "passive"))
      (node (ref "C51C") (pin "2") (pinfunction "2_2") (pintype "passive"))
      (node (ref "JP10C") (pin "10") (pintype "passive"))
      (node (ref "JP10C") (pin "11") (pintype "passive"))
      (node (ref "JP10C") (pin "16") (pintype "passive"))
      (node (ref "JP10C") (pin "19") (pintype "passive"))
      (node (ref "JP10C") (pin "22") (pintype "passive"))
      (node (ref "JP10C") (pin "25") (pintype "passive"))
      (node (ref "JP10C") (pin "28") (pintype "passive"))
      (node (ref "JP10C") (pin "31") (pintype "passive"))
      (node (ref "JP10C") (pin "34") (pintype "passive"))
      (node (ref "JP10C") (pin "37") (pintype "passive"))
      (node (ref "JP10C") (pin "40") (pintype "passive"))
      (node (ref "JP10C") (pin "43") (pintype "passive"))
      (node (ref "JP10C") (pin "46") (pintype "passive"))
      (node (ref "JP10C") (pin "6") (pintype "passive"))
      (node (ref "P10C") (pin "11") (pinfunction "11_11") (pintype "passive"))
      (node (ref "P10C") (pin "15") (pinfunction "15_15") (pintype "passive"))
      (node (ref "P10C") (pin "16") (pinfunction "16_16") (pintype "passive"))
      (node (ref "P10C") (pin "18") (pinfunction "18_18") (pintype "passive"))
      (node (ref "P10C") (pin "19") (pinfunction "19_19") (pintype "passive"))
      (node (ref "P10C") (pin "2") (pinfunction "2_2") (pintype "passive"))
      (node (ref "P10C") (pin "20") (pinfunction "20_20") (pintype "passive"))
      (node (ref "P10C") (pin "21") (pinfunction "21_21") (pintype "passive"))
      (node (ref "P10C") (pin "5") (pinfunction "5_5") (pintype "passive"))
      (node (ref "P10C") (pin "8") (pinfunction "8_8") (pintype "passive"))
      (node (ref "P11C") (pin "1") (pinfunction "1_1") (pintype "passive"))
      (node (ref "R17C") (pin "2") (pinfunction "2_2") (pintype "passive"))
      (node (ref "R25C") (pin "2") (pinfunction "2_2") (pintype "passive"))
      (node (ref "R31C") (pin "2") (pinfunction "2_2") (pintype "passive"))
      (node (ref "U10C") (pin "65") (pinfunction "EPGND_65") (pintype "power_in"))
      (node (ref "U11C") (pin "1") (pinfunction "GND_1") (pintype "power_in"))
    )
    (net (code "56") (name "Net-(C20C-Pad2)") (class "Default")
      (node (ref "C20C") (pin "2") (pinfunction "2_2") (pintype "passive"))
      (node (ref "J17C") (pin "1") (pinfunction "1_1") (pintype "passive"))
    )
    (net (code "57") (name "Net-(C21C-Pad2)") (class "Default")
      (node (ref "C21C") (pin "2") (pinfunction "2_2") (pintype "passive"))
      (node (ref "J18C") (pin "1") (pinfunction "1_1") (pintype "passive"))
    )
    (net (code "58") (name "Net-(C22C-Pad1)") (class "Default")
      (node (ref "C22C") (pin "1") (pinfunction "1_1") (pintype "passive"))
      (node (ref "J19C") (pin "1") (pinfunction "1_1") (pintype "passive"))
    )
    (net (code "59") (name "Net-(C24C-Pad1)") (class "Default")
      (node (ref "C24C") (pin "1") (pinfunction "1_1") (pintype "passive"))
      (node (ref "J20C") (pin "1") (pinfunction "1_1") (pintype "passive"))
    )
    (net (code "60") (name "Net-(U10CA-HPD)") (class "Default")
      (node (ref "R29C") (pin "1") (pinfunction "1_1") (pintype "passive"))
      (node (ref "U10C") (pin "5") (pinfunction "HPD_5") (pintype "passive"))
    )
    (net (code "61") (name "Net-(U10CA-REXT)") (class "Default")
      (node (ref "R23C") (pin "1") (pinfunction "1_1") (pintype "passive"))
      (node (ref "U10C") (pin "62") (pinfunction "REXT_62") (pintype "passive"))
    )
    (net (code "62") (name "Net-(U10CA-RXNE1)") (class "Default")
      (node (ref "J10C") (pin "1") (pinfunction "1_1") (pintype "passive"))
      (node (ref "R15C") (pin "2") (pinfunction "2_2") (pintype "passive"))
      (node (ref "U10C") (pin "29") (pinfunction "RXNE1_29") (pintype "input"))
    )
    (net (code "63") (name "Net-(U10CA-RXNE2)") (class "Default")
      (node (ref "J14C") (pin "1") (pinfunction "1_1") (pintype "passive"))
      (node (ref "R22C") (pin "2") (pinfunction "2_2") (pintype "passive"))
      (node (ref "U10C") (pin "44") (pinfunction "RXNE2_44") (pintype "input"))
    )
    (net (code "64") (name "Net-(U10CA-RXPE1)") (class "Default")
      (node (ref "J11C") (pin "1") (pinfunction "1_1") (pintype "passive"))
      (node (ref "R15C") (pin "1") (pinfunction "1_1") (pintype "passive"))
      (node (ref "U10C") (pin "30") (pinfunction "RXPE1_30") (pintype "input"))
    )
    (net (code "65") (name "Net-(U10CA-RXPE2)") (class "Default")
      (node (ref "J16C") (pin "1") (pinfunction "1_1") (pintype "passive"))
      (node (ref "R22C") (pin "1") (pinfunction "1_1") (pintype "passive"))
      (node (ref "U10C") (pin "45") (pinfunction "RXPE2_45") (pintype "input"))
    )
    (net (code "66") (name "Net-(U10CA-XTALIN)") (class "Default")
      (node (ref "C19C") (pin "2") (pinfunction "2_2") (pintype "passive"))
      (node (ref "R28C") (pin "1") (pinfunction "1_1") (pintype "passive"))
      (node (ref "U10C") (pin "3") (pinfunction "XTALIN_3") (pintype "passive"))
      (node (ref "Y10C") (pin "2") (pinfunction "OSC2_2") (pintype "passive"))
    )
    (net (code "67") (name "Net-(U10CA-XTALOUT)") (class "Default")
      (node (ref "C18C") (pin "2") (pinfunction "2_2") (pintype "passive"))
      (node (ref "R28C") (pin "2") (pinfunction "2_2") (pintype "passive"))
      (node (ref "U10C") (pin "2") (pinfunction "XTALOUT_2") (pintype "passive"))
      (node (ref "Y10C") (pin "1") (pinfunction "OSC1_1") (pintype "passive"))
    )
    (net (code "68") (name "Net-(U10CB-PVCC2)") (class "Default")
      (node (ref "C44C") (pin "1") (pinfunction "1_1") (pintype "passive"))
      (node (ref "R27C") (pin "2") (pinfunction "2_2") (pintype "passive"))
      (node (ref "U10C") (pin "4") (pinfunction "PVCC2_4") (pintype "power_in"))
    )
    (net (code "69") (name "P1.8VA") (class "Default")
      (node (ref "C22P") (pin "2") (pinfunction "2_2") (pintype "passive"))
      (node (ref "C30C") (pin "1") (pinfunction "1_1") (pintype "passive"))
      (node (ref "C31C") (pin "1") (pinfunction "1_1") (pintype "passive"))
      (node (ref "C32C") (pin "1") (pinfunction "1_1") (pintype "passive"))
      (node (ref "C33C") (pin "1") (pinfunction "1_1") (pintype "passive"))
      (node (ref "C39C") (pin "1") (pinfunction "1_1") (pintype "passive"))
      (node (ref "C40C") (pin "1") (pinfunction "1_1") (pintype "passive"))
      (node (ref "C41C") (pin "1") (pinfunction "1_1") (pintype "passive"))
      (node (ref "C42C") (pin "1") (pinfunction "1_1") (pintype "passive"))
      (node (ref "C43C") (pin "1") (pinfunction "1_1") (pintype "passive"))
      (node (ref "R23C") (pin "2") (pinfunction "2_2") (pintype "passive"))
      (node (ref "U10C") (pin "16") (pinfunction "ANVDD_16") (pintype "power_in"))
      (node (ref "U10C") (pin "26") (pinfunction "ANVDD_26") (pintype "power_in"))
      (node (ref "U10C") (pin "33") (pinfunction "ANVDD_33") (pintype "power_in"))
      (node (ref "U10C") (pin "41") (pinfunction "ANVDD_41") (pintype "power_in"))
      (node (ref "U10C") (pin "49") (pinfunction "AVCC18_49") (pintype "power_in"))
      (node (ref "U10C") (pin "52") (pinfunction "AVCC18_52") (pintype "power_in"))
      (node (ref "U10C") (pin "55") (pinfunction "AVCC18_55") (pintype "power_in"))
      (node (ref "U10C") (pin "58") (pinfunction "AVCC18_58") (pintype "power_in"))
      (node (ref "U10C") (pin "61") (pinfunction "AVCC18_61") (pintype "power_in"))
    )
    (net (code "70") (name "P1.8VA_DP_PLL") (class "Default")
      (node (ref "C45C") (pin "1") (pinfunction "1_1") (pintype "passive"))
      (node (ref "C46C") (pin "1") (pinfunction "1_1") (pintype "passive"))
      (node (ref "R27C") (pin "1") (pinfunction "1_1") (pintype "passive"))
      (node (ref "U10C") (pin "63") (pinfunction "PVCC1_63") (pintype "power_in"))
      (node (ref "U10C") (pin "64") (pinfunction "PVCC0_64") (pintype "power_in"))
    )
    (net (code "71") (name "P1.8VA_LVDS_PLL") (class "Default")
      (node (ref "C47C") (pin "1") (pinfunction "1_1") (pintype "passive"))
      (node (ref "C48C") (pin "1") (pinfunction "1_1") (pintype "passive"))
      (node (ref "U10C") (pin "31") (pinfunction "APVDD_31") (pintype "power_in"))
    )
    (net (code "72") (name "P1.8VD") (class "Default")
      (node (ref "C26C") (pin "1") (pinfunction "1_1") (pintype "passive"))
      (node (ref "C27C") (pin "1") (pinfunction "1_1") (pintype "passive"))
      (node (ref "C28C") (pin "1") (pinfunction "1_1") (pintype "passive"))
      (node (ref "C29C") (pin "1") (pinfunction "1_1") (pintype "passive"))
      (node (ref "U10C") (pin "11") (pinfunction "IVDD_11") (pintype "power_in"))
      (node (ref "U10C") (pin "32") (pinfunction "IVDD_32") (pintype "power_in"))
      (node (ref "U10C") (pin "46") (pinfunction "IVDD_46") (pintype "power_in"))
      (node (ref "U10C") (pin "6") (pinfunction "IVDD_6") (pintype "power_in"))
    )
    (net (code "73") (name "P3.3V") (class "Default")
      (node (ref "C16C") (pin "1") (pinfunction "1_1") (pintype "passive"))
      (node (ref "C17C") (pin "2") (pinfunction "2_2") (pintype "passive"))
      (node (ref "C25C") (pin "1") (pinfunction "1_1") (pintype "passive"))
      (node (ref "C36C") (pin "1") (pinfunction "1_1") (pintype "passive"))
      (node (ref "C50C") (pin "2") (pinfunction "2_2") (pintype "passive"))
      (node (ref "JP10C") (pin "12") (pintype "passive"))
      (node (ref "JP10C") (pin "13") (pintype "passive"))
      (node (ref "JP10C") (pin "14") (pintype "passive"))
      (node (ref "JP10C") (pin "15") (pintype "passive"))
      (node (ref "P10C") (pin "12") (pinfunction "12_12") (pintype "passive"))
      (node (ref "P10C") (pin "13") (pinfunction "13_13") (pintype "passive"))
      (node (ref "R16C") (pin "1") (pinfunction "1_1") (pintype "passive"))
      (node (ref "R24C") (pin "1") (pinfunction "1_1") (pintype "passive"))
      (node (ref "R26C") (pin "1") (pinfunction "1_1") (pintype "passive"))
      (node (ref "R30C") (pin "2") (pinfunction "2_2") (pintype "passive"))
      (node (ref "U10C") (pin "12") (pinfunction "OVDD_12") (pintype "power_in"))
      (node (ref "U11C") (pin "3") (pinfunction "VCC_3") (pintype "power_in"))
    )
    (net (code "74") (name "P3.3VA") (class "Default")
      (node (ref "C37C") (pin "1") (pinfunction "1_1") (pintype "passive"))
      (node (ref "C38C") (pin "1") (pinfunction "1_1") (pintype "passive"))
      (node (ref "U10C") (pin "21") (pinfunction "AVCC_21") (pintype "power_in"))
      (node (ref "U10C") (pin "38") (pinfunction "AVCC_38") (pintype "power_in"))
    )
    (net (code "75") (name "unconnected-(P10C-Pad1)") (class "Default")
      (node (ref "P10C") (pin "1") (pinfunction "1_1") (pintype "passive"))
    )
    (net (code "76") (name "unconnected-(P10C-Pad14)") (class "Default")
      (node (ref "P10C") (pin "14") (pinfunction "14_14") (pintype "passive"))
    )
    (net (code "77") (name "unconnected-(P10C-Pad24)") (class "Default")
      (node (ref "P10C") (pin "24") (pinfunction "24_24") (pintype "passive"))
    )
    (net (code "78") (name "unconnected-(P10C-Pad25)") (class "Default")
      (node (ref "P10C") (pin "25") (pinfunction "25_25") (pintype "passive"))
    )
    (net (code "79") (name "unconnected-(P10C-Pad30)") (class "Default")
      (node (ref "P10C") (pin "30") (pinfunction "30_30") (pintype "passive"))
    )
  )
)
